# Ethernet_Controller.net
KiCad netlist of a schematic drawn in Altium Designer
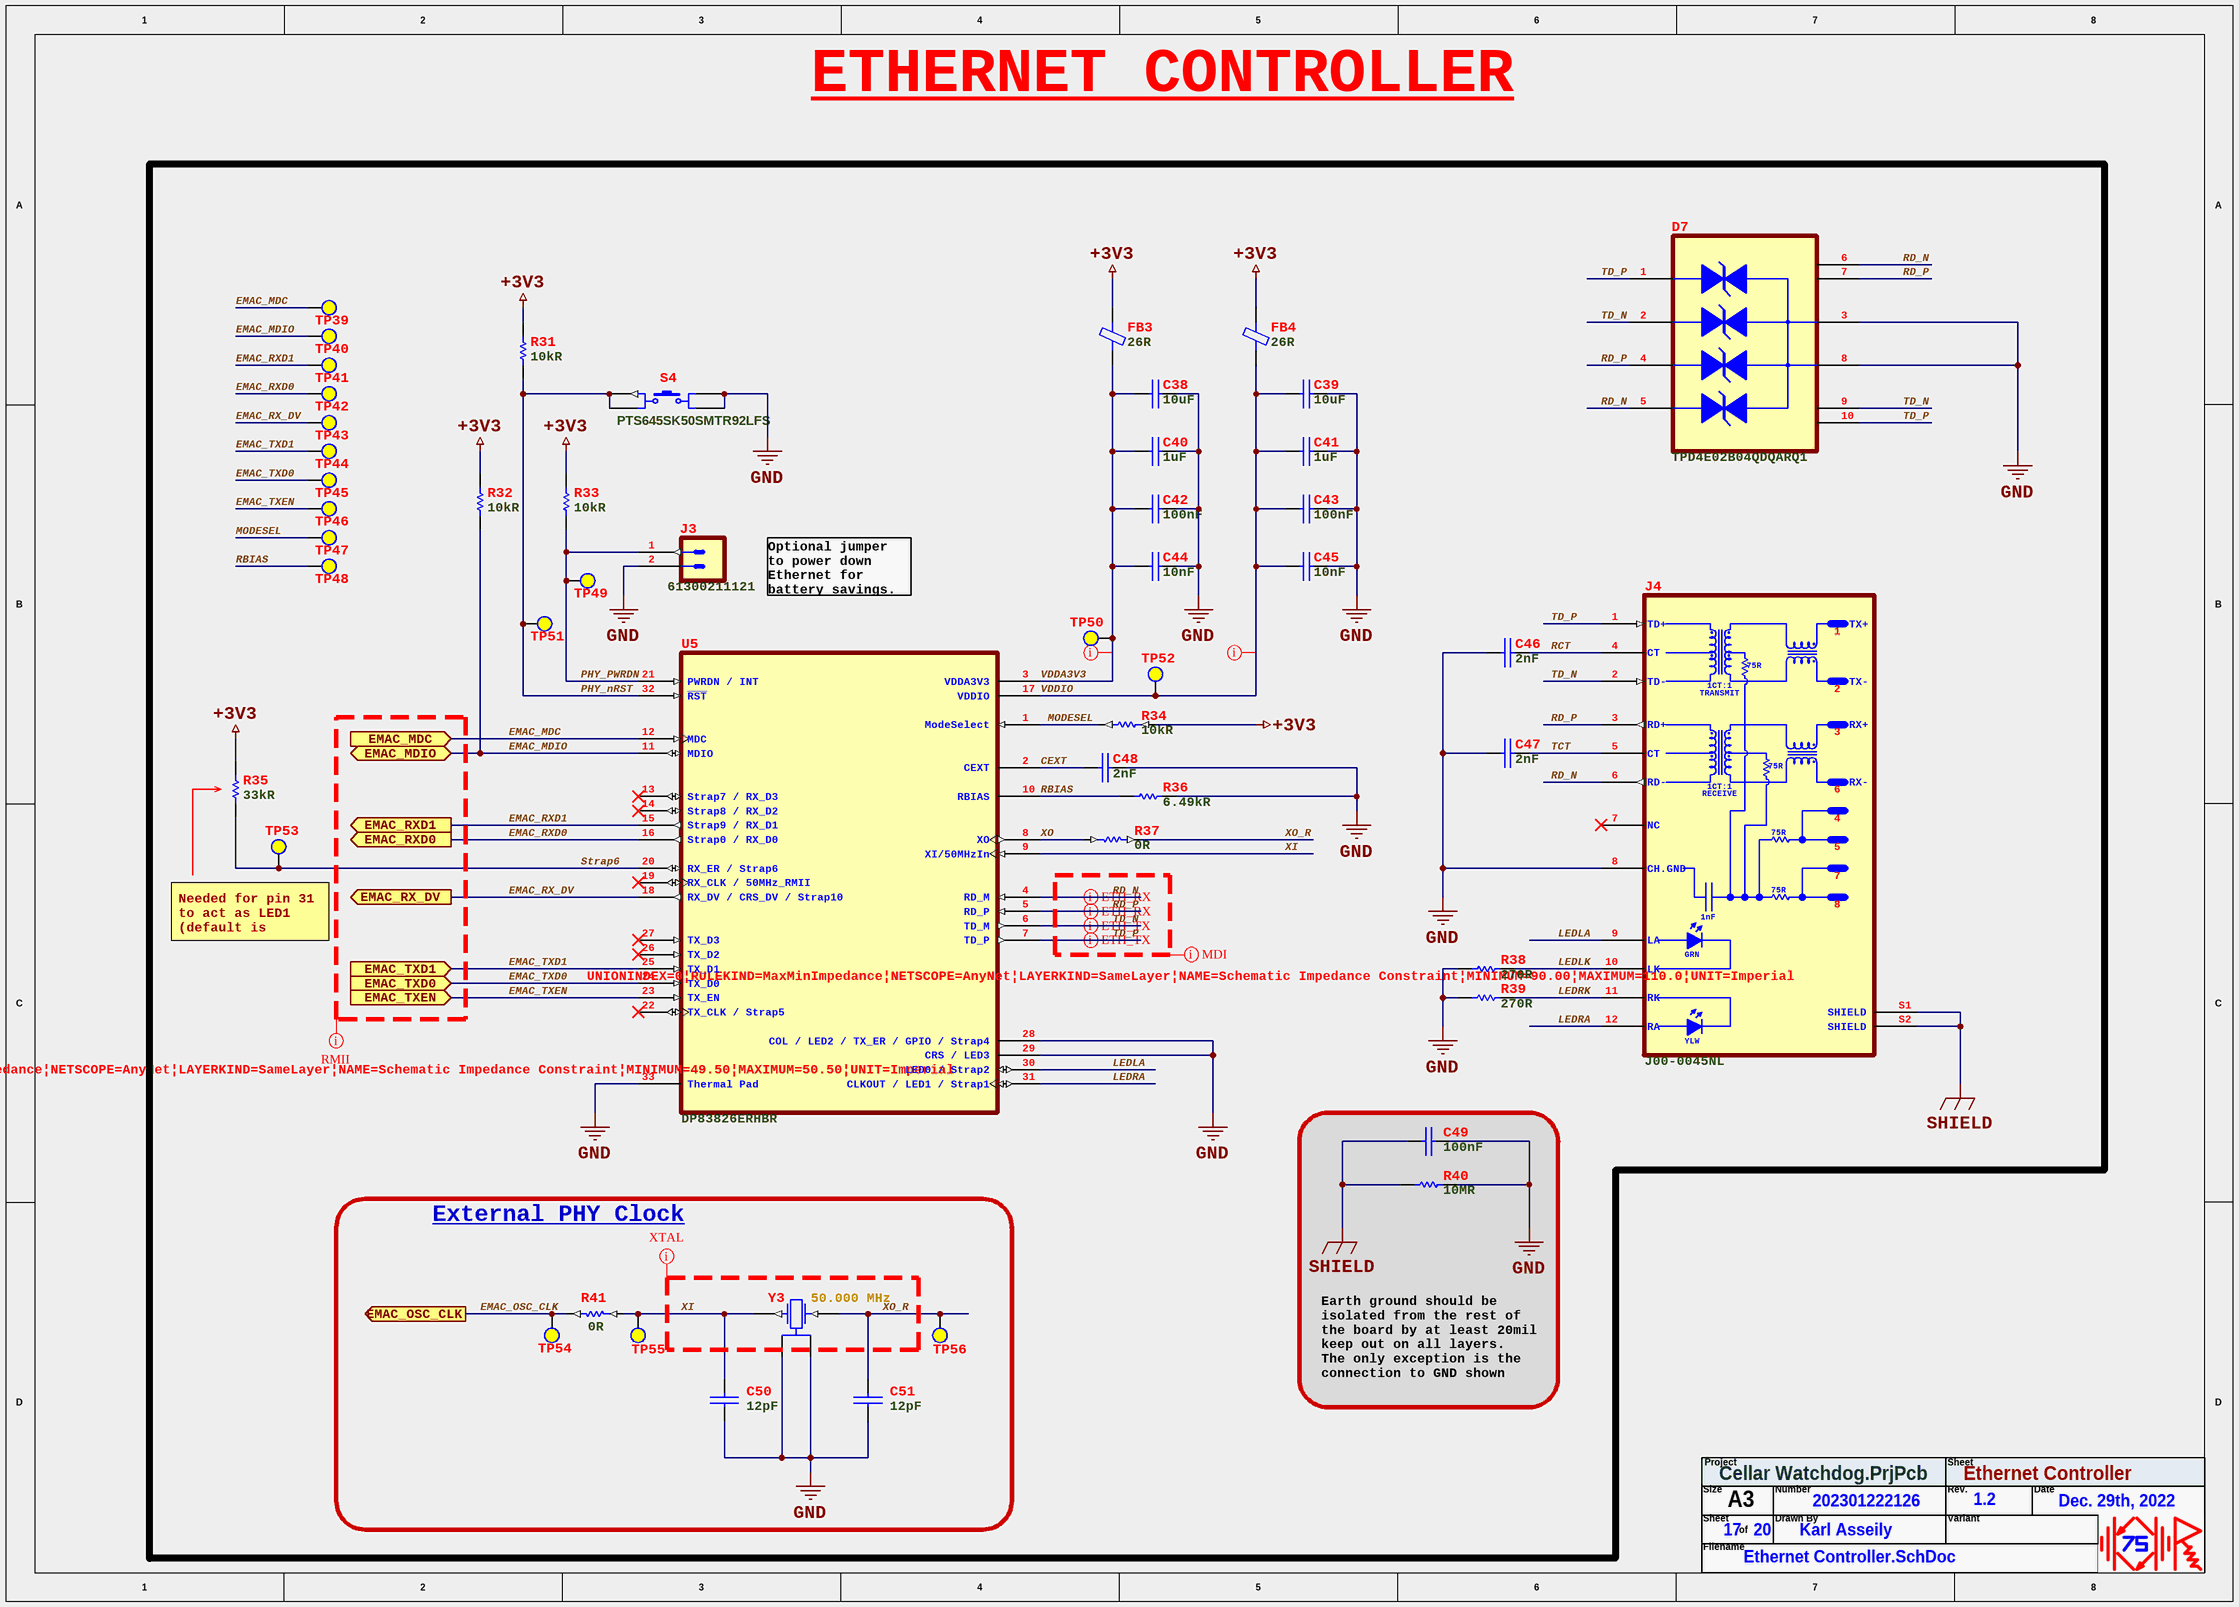
[diagram p0: Ethernet Controller.SchDoc]

(export (version "E")
  (design (tool "Eeschema 10.0.6"))
  (components
    (comp (ref "C38")
      (value "10uF")
      (footprint "CAP_1206")
      (description "10 µF ±10% 25V Ceramic Capacitor X7R 1206 (3216 Metric)")
      (fields
        (field (name "MANUFACTURER") "Yageo")
        (field (name "MANUFACTURER PART NUMBER") "CC1206KKX7R8BB106")
      )
      (libsource (lib "Cellar Watchdog") (part "CAP_10uF-25V-10%_1206"))
    )
    (comp (ref "C39")
      (value "10uF")
      (footprint "CAP_1206")
      (description "10 µF ±10% 25V Ceramic Capacitor X7R 1206 (3216 Metric)")
      (fields
        (field (name "MANUFACTURER") "Yageo")
        (field (name "MANUFACTURER PART NUMBER") "CC1206KKX7R8BB106")
      )
      (libsource (lib "Cellar Watchdog") (part "CAP_10uF-25V-10%_1206"))
    )
    (comp (ref "C40")
      (value "1uF")
      (footprint "CAP_0805")
      (description "1 µF ±10% 16V Ceramic Capacitor X7R 0603 (1608 Metric)")
      (fields
        (field (name "MANUFACTURER") "Yageo")
        (field (name "MANUFACTURER PART NUMBER") "CC0603KRX7R7BB105")
      )
      (libsource (lib "Cellar Watchdog") (part "CAP_1uF-16V-10%_0603"))
    )
    (comp (ref "C41")
      (value "1uF")
      (footprint "CAP_0805")
      (description "1 µF ±10% 16V Ceramic Capacitor X7R 0603 (1608 Metric)")
      (fields
        (field (name "MANUFACTURER") "Yageo")
        (field (name "MANUFACTURER PART NUMBER") "CC0603KRX7R7BB105")
      )
      (libsource (lib "Cellar Watchdog") (part "CAP_1uF-16V-10%_0603"))
    )
    (comp (ref "C42")
      (value "100nF")
      (footprint "CAP_0603")
      (description "0.1 µF ±10% 50V Ceramic Capacitor X7R 0603 (1608 Metric)")
      (fields
        (field (name "MANUFACTURER") "Yageo")
        (field (name "MANUFACTURER PART NUMBER") "CC0603KRX7R9BB104")
      )
      (libsource (lib "Cellar Watchdog") (part "CAP_0.1uF-50V-10%_0603"))
    )
    (comp (ref "C43")
      (value "100nF")
      (footprint "CAP_0603")
      (description "0.1 µF ±10% 50V Ceramic Capacitor X7R 0603 (1608 Metric)")
      (fields
        (field (name "MANUFACTURER") "Yageo")
        (field (name "MANUFACTURER PART NUMBER") "CC0603KRX7R9BB104")
      )
      (libsource (lib "Cellar Watchdog") (part "CAP_0.1uF-50V-10%_0603"))
    )
    (comp (ref "C44")
      (value "10nF")
      (footprint "CAP_0603")
      (description "10000 pF ±10% 50V Ceramic Capacitor X7R 0603 (1608 Metric)")
      (fields
        (field (name "MANUFACTURER") "Yageo")
        (field (name "MANUFACTURER PART NUMBER") "CC0603KRX7R9BB103")
      )
      (libsource (lib "Cellar Watchdog") (part "CAP_10nF-50V-10%_0603"))
    )
    (comp (ref "C45")
      (value "10nF")
      (footprint "CAP_0603")
      (description "10000 pF ±10% 50V Ceramic Capacitor X7R 0603 (1608 Metric)")
      (fields
        (field (name "MANUFACTURER") "Yageo")
        (field (name "MANUFACTURER PART NUMBER") "CC0603KRX7R9BB103")
      )
      (libsource (lib "Cellar Watchdog") (part "CAP_10nF-50V-10%_0603"))
    )
    (comp (ref "C46")
      (value "2nF")
      (footprint "CAP_0603")
      (description "2000 pF ±10% 50V Ceramic Capacitor X7R 0603 (1608 Metric)")
      (fields
        (field (name "MANUFACTURER") "Yageo")
        (field (name "MANUFACTURER PART NUMBER") "CC0603KRX7R9BB202")
      )
      (libsource (lib "Cellar Watchdog") (part "CAP_2nF-50V-10%_0603"))
    )
    (comp (ref "C47")
      (value "2nF")
      (footprint "CAP_0603")
      (description "2000 pF ±10% 50V Ceramic Capacitor X7R 0603 (1608 Metric)")
      (fields
        (field (name "MANUFACTURER") "Yageo")
        (field (name "MANUFACTURER PART NUMBER") "CC0603KRX7R9BB202")
      )
      (libsource (lib "Cellar Watchdog") (part "CAP_2nF-50V-10%_0603"))
    )
    (comp (ref "C48")
      (value "2nF")
      (footprint "CAP_0603")
      (description "2000 pF ±10% 50V Ceramic Capacitor X7R 0603 (1608 Metric)")
      (fields
        (field (name "MANUFACTURER") "Yageo")
        (field (name "MANUFACTURER PART NUMBER") "CC0603KRX7R9BB202")
      )
      (libsource (lib "Cellar Watchdog") (part "CAP_2nF-50V-10%_0603"))
    )
    (comp (ref "C49")
      (value "100nF")
      (footprint "CAP_1206")
      (description "0.1 µF ±5% 100V Ceramic Capacitor X7R 1206 (3216 Metric)")
      (fields
        (field (name "MANUFACTURER") "Yageo")
        (field (name "MANUFACTURER PART NUMBER") "CC1206JKX7R0BB104")
      )
      (libsource (lib "Cellar Watchdog") (part "CAP_0.1uF-100V-5%_1206"))
    )
    (comp (ref "C50")
      (value "12pF")
      (footprint "CAP_0603")
      (description "12 pF ±5% 50V Ceramic Capacitor C0G, NP0 0603 (1608 Metric)")
      (fields
        (field (name "MANUFACTURER") "Yageo")
        (field (name "MANUFACTURER PART NUMBER") "CC0603JRNPO9BN120")
      )
      (libsource (lib "Cellar Watchdog") (part "CAP_12pf-50V-5%_0603"))
    )
    (comp (ref "C51")
      (value "12pF")
      (footprint "CAP_0603")
      (description "12 pF ±5% 50V Ceramic Capacitor C0G, NP0 0603 (1608 Metric)")
      (fields
        (field (name "MANUFACTURER") "Yageo")
        (field (name "MANUFACTURER PART NUMBER") "CC0603JRNPO9BN120")
      )
      (libsource (lib "Cellar Watchdog") (part "CAP_12pf-50V-5%_0603"))
    )
    (comp (ref "D7")
      (value "TPD4E02B04QDQARQ1")
      (footprint "DIO-T-A_10-USON")
      (description "8.8V Clamp 2A (8/20µs) Ipp Tvs Diode Surface Mount 10-USON (2.5x1)")
      (fields (field (name "MANUFACTURER") "Texas Instruments"))
      (libsource (lib "Cellar Watchdog") (part "DIO-T-A-BI_5.5V-8.8V-2A_10-USON"))
    )
    (comp (ref "FB3")
      (value "26R")
      (footprint "FB_0603")
      (description "26 Ohms @ 100 MHz 1 Power Line Ferrite Bead 0603 (1608 Metric) 6A 7mOhm")
      (fields
        (field (name "MANUFACTURER") "Murata")
        (field (name "MANUFACTURER PART NUMBER") "BLM18SG260TZ1D")
      )
      (libsource (lib "Cellar Watchdog") (part "FB_26R-100MHz-6A_0603"))
    )
    (comp (ref "FB4")
      (value "26R")
      (footprint "FB_0603")
      (description "26 Ohms @ 100 MHz 1 Power Line Ferrite Bead 0603 (1608 Metric) 6A 7mOhm")
      (fields
        (field (name "MANUFACTURER") "Murata")
        (field (name "MANUFACTURER PART NUMBER") "BLM18SG260TZ1D")
      )
      (libsource (lib "Cellar Watchdog") (part "FB_26R-100MHz-6A_0603"))
    )
    (comp (ref "J3")
      (value "61300211121")
      (footprint "CON_PLG_HDR-2x1-100")
      (description "Connector Header Through Hole 2 position 0.100\" (2.54mm)")
      (fields (field (name "MANUFACTURER") "Wurth Electronics"))
      (libsource (lib "Cellar Watchdog") (part "CON-PLG-HDR_2x1-100-ST_TH"))
    )
    (comp (ref "J4")
      (value "J00-0045NL")
      (footprint "CON-RCPT_RJ_PULSE_J00-0045NL")
      (description "1 Port RJ45 Through Hole 10/100 Base-TX, AutoMDIX")
      (fields (field (name "MANUFACTURER") "Pulse"))
      (libsource (lib "Cellar Watchdog") (part "CON-RCPT_RJ_J00-0045NL"))
    )
    (comp (ref "R31")
      (value "10kR")
      (footprint "RES_0603")
      (description "10 kOhms ±1% 0.1W, 1/10W Chip Resistor 0603 (1608 Metric) Moisture Resistant Thick Film")
      (fields
        (field (name "MANUFACTURER") "Yageo")
        (field (name "MANUFACTURER PART NUMBER") "RC0603FR-0710KL")
      )
      (libsource (lib "Cellar Watchdog") (part "RES_10kR-100mW-1%_0603"))
    )
    (comp (ref "R32")
      (value "10kR")
      (footprint "RES_0603")
      (description "10 kOhms ±1% 0.1W, 1/10W Chip Resistor 0603 (1608 Metric) Moisture Resistant Thick Film")
      (fields
        (field (name "MANUFACTURER") "Yageo")
        (field (name "MANUFACTURER PART NUMBER") "RC0603FR-0710KL")
      )
      (libsource (lib "Cellar Watchdog") (part "RES_10kR-100mW-1%_0603"))
    )
    (comp (ref "R33")
      (value "10kR")
      (footprint "RES_0603")
      (description "10 kOhms ±1% 0.1W, 1/10W Chip Resistor 0603 (1608 Metric) Moisture Resistant Thick Film")
      (fields
        (field (name "MANUFACTURER") "Yageo")
        (field (name "MANUFACTURER PART NUMBER") "RC0603FR-0710KL")
      )
      (libsource (lib "Cellar Watchdog") (part "RES_10kR-100mW-1%_0603"))
    )
    (comp (ref "R34")
      (value "10kR")
      (footprint "RES_0603")
      (description "10 kOhms ±1% 0.1W, 1/10W Chip Resistor 0603 (1608 Metric) Moisture Resistant Thick Film")
      (fields
        (field (name "MANUFACTURER") "Yageo")
        (field (name "MANUFACTURER PART NUMBER") "RC0603FR-0710KL")
      )
      (libsource (lib "Cellar Watchdog") (part "RES_10kR-100mW-1%_0603"))
    )
    (comp (ref "R35")
      (value "33kR")
      (footprint "RES_0603")
      (description "33 kOhms ±1% 0.1W, 1/10W Chip Resistor 0603 (1608 Metric) Moisture Resistant Thick Film")
      (fields
        (field (name "MANUFACTURER") "Yageo")
        (field (name "MANUFACTURER PART NUMBER") "RC0603FR-0733KL")
      )
      (libsource (lib "Cellar Watchdog") (part "RES_33kR-100mW-1%_0603"))
    )
    (comp (ref "R36")
      (value "6.49kR")
      (footprint "RES_0603")
      (description "6.49 kOhms ±1% 0.1W, 1/10W Chip Resistor 0603 (1608 Metric) Moisture Resistant Thick Film")
      (fields
        (field (name "MANUFACTURER") "Yageo")
        (field (name "MANUFACTURER PART NUMBER") "RC0603FR-076K49L")
      )
      (libsource (lib "Cellar Watchdog") (part "RES_6.49kR-100mW-1%_0603"))
    )
    (comp (ref "R37")
      (value "0R")
      (footprint "RES_0603")
      (description "0 Ohms Jumper Chip Resistor 0603 (1608 Metric) Moisture Resistant Thick Film")
      (fields
        (field (name "MANUFACTURER") "Yageo")
        (field (name "MANUFACTURER PART NUMBER") "RC0603FR-070RL")
      )
      (libsource (lib "Cellar Watchdog") (part "RES_0R-100mW-1%_0603"))
    )
    (comp (ref "R38")
      (value "270R")
      (footprint "RES_0603")
      (description "270 Ohms ±1% 0.1W, 1/10W Chip Resistor 0603 (1608 Metric) Moisture Resistant Thick Film")
      (fields
        (field (name "MANUFACTURER") "Yageo")
        (field (name "MANUFACTURER PART NUMBER") "RC0603FR-07270RL")
      )
      (libsource (lib "Cellar Watchdog") (part "RES_270R-100mW-1%_0603"))
    )
    (comp (ref "R39")
      (value "270R")
      (footprint "RES_0603")
      (description "270 Ohms ±1% 0.1W, 1/10W Chip Resistor 0603 (1608 Metric) Moisture Resistant Thick Film")
      (fields
        (field (name "MANUFACTURER") "Yageo")
        (field (name "MANUFACTURER PART NUMBER") "RC0603FR-07270RL")
      )
      (libsource (lib "Cellar Watchdog") (part "RES_270R-100mW-1%_0603"))
    )
    (comp (ref "R40")
      (value "10MR")
      (footprint "RES_2512")
      (description "10 MOhms ±1% 1W Chip Resistor 2512 (6432 Metric) Moisture Resistant Thick Film")
      (fields
        (field (name "MANUFACTURER") "Yageo")
        (field (name "MANUFACTURER PART NUMBER") "RC2512FK-0710ML")
      )
      (libsource (lib "Cellar Watchdog") (part "RES_10MR-1W-1%_2512"))
    )
    (comp (ref "R41")
      (value "0R")
      (footprint "RES_0603")
      (description "0 Ohms Jumper Chip Resistor 0603 (1608 Metric) Moisture Resistant Thick Film")
      (fields
        (field (name "MANUFACTURER") "Yageo")
        (field (name "MANUFACTURER PART NUMBER") "RC0603FR-070RL")
      )
      (libsource (lib "Cellar Watchdog") (part "RES_0R-100mW-1%_0603"))
    )
    (comp (ref "S4")
      (value "PTS645SK50SMTR92LFS")
      (footprint "SW_TACTILE-SPST_PTS645SK50SMTR92LFS_SMD")
      (description "Tactile Switch SPST-NO Top Actuated Surface Mount")
      (fields (field (name "MANUFACTURER") "ITT C&K"))
      (libsource (lib "Cellar Watchdog") (part "SW4-NO-SPST_PTS645SK50SMTR92LFS_SMD"))
    )
    (comp (ref "TP39")
      (value "EMAC_MDC")
      (footprint "TEST POINT PAD")
      (description "PCB Test Point")
      (libsource (lib "Cellar Watchdog") (part "Test Point"))
    )
    (comp (ref "TP40")
      (value "EMAC_MDIO")
      (footprint "TEST POINT PAD")
      (description "PCB Test Point")
      (libsource (lib "Cellar Watchdog") (part "Test Point"))
    )
    (comp (ref "TP41")
      (value "EMAC_RXD1")
      (footprint "TEST POINT PAD")
      (description "PCB Test Point")
      (libsource (lib "Cellar Watchdog") (part "Test Point"))
    )
    (comp (ref "TP42")
      (value "EMAC_RXD0")
      (footprint "TEST POINT PAD")
      (description "PCB Test Point")
      (libsource (lib "Cellar Watchdog") (part "Test Point"))
    )
    (comp (ref "TP43")
      (value "EMAC_RX_DV")
      (footprint "TEST POINT PAD")
      (description "PCB Test Point")
      (libsource (lib "Cellar Watchdog") (part "Test Point"))
    )
    (comp (ref "TP44")
      (value "EMAC_TXD1")
      (footprint "TEST POINT PAD")
      (description "PCB Test Point")
      (libsource (lib "Cellar Watchdog") (part "Test Point"))
    )
    (comp (ref "TP45")
      (value "EMAC_TXD0")
      (footprint "TEST POINT PAD")
      (description "PCB Test Point")
      (libsource (lib "Cellar Watchdog") (part "Test Point"))
    )
    (comp (ref "TP46")
      (value "EMAC_TXEN")
      (footprint "TEST POINT PAD")
      (description "PCB Test Point")
      (libsource (lib "Cellar Watchdog") (part "Test Point"))
    )
    (comp (ref "TP47")
      (value "MODESEL")
      (footprint "TEST POINT PAD")
      (description "PCB Test Point")
      (libsource (lib "Cellar Watchdog") (part "Test Point"))
    )
    (comp (ref "TP48")
      (value "RBIAS")
      (footprint "TEST POINT PAD")
      (description "PCB Test Point")
      (libsource (lib "Cellar Watchdog") (part "Test Point"))
    )
    (comp (ref "TP49")
      (value "PHY_PWRDN")
      (footprint "TEST POINT PAD")
      (description "PCB Test Point")
      (libsource (lib "Cellar Watchdog") (part "Test Point"))
    )
    (comp (ref "TP50")
      (value "VDDA3V3")
      (footprint "TEST POINT PAD")
      (description "PCB Test Point")
      (libsource (lib "Cellar Watchdog") (part "Test Point"))
    )
    (comp (ref "TP51")
      (value "PHY_nRST")
      (footprint "TEST POINT HOLE")
      (description "PCB Test Point")
      (libsource (lib "Cellar Watchdog") (part "Test Point"))
    )
    (comp (ref "TP52")
      (value "VDDIO")
      (footprint "TEST POINT PAD")
      (description "PCB Test Point")
      (libsource (lib "Cellar Watchdog") (part "Test Point"))
    )
    (comp (ref "TP53")
      (value "Strap6")
      (footprint "TEST POINT PAD")
      (description "PCB Test Point")
      (libsource (lib "Cellar Watchdog") (part "Test Point"))
    )
    (comp (ref "TP54")
      (value "EMAC_OSC_CLK")
      (footprint "TEST POINT PAD")
      (description "PCB Test Point")
      (libsource (lib "Cellar Watchdog") (part "Test Point"))
    )
    (comp (ref "TP55")
      (value "50MHz IN EMAC")
      (footprint "TEST POINT HOLE")
      (description "PCB Test Point")
      (libsource (lib "Cellar Watchdog") (part "Test Point"))
    )
    (comp (ref "TP56")
      (value "50MHz OUT EMAC")
      (footprint "TEST POINT HOLE")
      (description "PCB Test Point")
      (libsource (lib "Cellar Watchdog") (part "Test Point"))
    )
    (comp (ref "U5")
      (value "DP83826ERHBR")
      (footprint "IC_QFN50P500X500X100-33N-D")
      (description "Ethernet Controller 10/100 Base-T/TX PHY MII, RMII Interface 32-VQFN (5x5)")
      (fields (field (name "MANUFACTURER") "Texas Instruments"))
      (libsource (lib "Cellar Watchdog") (part "IC_DP83826ERHBR"))
    )
    (comp (ref "Y3")
      (value "ECS-500-10-33-RTN-TR")
      (footprint "XTAL_ECS-500-10-33-RTN-TR")
      (description "50 MHz ±15ppm Crystal 10pF 40 Ohms 4-SMD, No Lead")
      (fields (field (name "MANUFACTURER") "ECS International") (field (name "FREQUENCY") "50.000 MHz"))
      (libsource (lib "Cellar Watchdog") (part "XTAL_50.000MHz-10pF_4-SMD"))
    )
  )
  (nets
    (net (code "1") (name "+3V3") (class "Default")
      (node (ref "FB3") (pin "2") (pinfunction "2_2") (pintype "passive"))
      (node (ref "FB4") (pin "2") (pinfunction "2_2") (pintype "passive"))
      (node (ref "R31") (pin "2") (pinfunction "2_2") (pintype "passive"))
      (node (ref "R32") (pin "2") (pinfunction "2_2") (pintype "passive"))
      (node (ref "R33") (pin "2") (pinfunction "2_2") (pintype "passive"))
      (node (ref "R34") (pin "2") (pinfunction "2_2") (pintype "passive"))
      (node (ref "R35") (pin "2") (pinfunction "2_2") (pintype "passive"))
    )
    (net (code "2") (name "/CEXT") (class "Default")
      (node (ref "C48") (pin "1") (pinfunction "1_1") (pintype "passive"))
      (node (ref "U5") (pin "2") (pinfunction "CEXT_2") (pintype "passive"))
    )
    (net (code "3") (name "/EMAC_MDC") (class "Default")
      (node (ref "TP39") (pin "TP") (pinfunction "TP_TP") (pintype "passive"))
      (node (ref "U5") (pin "12") (pinfunction "MDC_12") (pintype "input"))
    )
    (net (code "4") (name "/EMAC_MDIO") (class "Default")
      (node (ref "R32") (pin "1") (pinfunction "1_1") (pintype "passive"))
      (node (ref "TP40") (pin "TP") (pinfunction "TP_TP") (pintype "passive"))
      (node (ref "U5") (pin "11") (pinfunction "MDIO_11") (pintype "bidirectional"))
    )
    (net (code "5") (name "/EMAC_OSC_CLK") (class "Default")
      (node (ref "R41") (pin "1") (pinfunction "1_1") (pintype "input"))
      (node (ref "TP54") (pin "TP") (pinfunction "TP_TP") (pintype "passive"))
    )
    (net (code "6") (name "/EMAC_RXD0") (class "Default")
      (node (ref "TP42") (pin "TP") (pinfunction "TP_TP") (pintype "passive"))
      (node (ref "U5") (pin "16") (pinfunction "Strap0_/_RX_D0_16") (pintype "output"))
    )
    (net (code "7") (name "/EMAC_RXD1") (class "Default")
      (node (ref "TP41") (pin "TP") (pinfunction "TP_TP") (pintype "passive"))
      (node (ref "U5") (pin "15") (pinfunction "Strap9_/_RX_D1_15") (pintype "output"))
    )
    (net (code "8") (name "/EMAC_RX_DV") (class "Default")
      (node (ref "TP43") (pin "TP") (pinfunction "TP_TP") (pintype "passive"))
      (node (ref "U5") (pin "18") (pinfunction "RX_DV_/_CRS_DV_/_Strap10_18") (pintype "output"))
    )
    (net (code "9") (name "/EMAC_TXD0") (class "Default")
      (node (ref "TP45") (pin "TP") (pinfunction "TP_TP") (pintype "passive"))
      (node (ref "U5") (pin "24") (pinfunction "TX_D0_24") (pintype "input"))
    )
    (net (code "10") (name "/EMAC_TXD1") (class "Default")
      (node (ref "TP44") (pin "TP") (pinfunction "TP_TP") (pintype "passive"))
      (node (ref "U5") (pin "25") (pinfunction "TX_D1_25") (pintype "input"))
    )
    (net (code "11") (name "/EMAC_TXEN") (class "Default")
      (node (ref "TP46") (pin "TP") (pinfunction "TP_TP") (pintype "passive"))
      (node (ref "U5") (pin "23") (pinfunction "TX_EN_23") (pintype "input"))
    )
    (net (code "12") (name "/LEDLA") (class "Default")
      (node (ref "J4") (pin "9") (pinfunction "LA_9") (pintype "passive"))
      (node (ref "U5") (pin "30") (pinfunction "LED0_/_Strap2_30") (pintype "bidirectional"))
    )
    (net (code "13") (name "/LEDLK") (class "Default")
      (node (ref "J4") (pin "10") (pinfunction "LK_10") (pintype "passive"))
      (node (ref "R38") (pin "1") (pinfunction "1_1") (pintype "passive"))
    )
    (net (code "14") (name "/LEDRA") (class "Default")
      (node (ref "J4") (pin "12") (pinfunction "RA_12") (pintype "passive"))
      (node (ref "U5") (pin "31") (pinfunction "CLKOUT_/_LED1_/_Strap1_31") (pintype "bidirectional"))
    )
    (net (code "15") (name "/LEDRK") (class "Default")
      (node (ref "J4") (pin "11") (pinfunction "RK_11") (pintype "passive"))
      (node (ref "R39") (pin "1") (pinfunction "1_1") (pintype "passive"))
    )
    (net (code "16") (name "/MODESEL") (class "Default")
      (node (ref "R34") (pin "1") (pinfunction "1_1") (pintype "passive"))
      (node (ref "TP47") (pin "TP") (pinfunction "TP_TP") (pintype "passive"))
      (node (ref "U5") (pin "1") (pinfunction "ModeSelect_1") (pintype "input"))
    )
    (net (code "17") (name "/PHY_PWRDN") (class "Default")
      (node (ref "J3") (pin "1") (pinfunction "1_1") (pintype "output"))
      (node (ref "R33") (pin "1") (pinfunction "1_1") (pintype "passive"))
      (node (ref "TP49") (pin "TP") (pinfunction "TP_TP") (pintype "passive"))
      (node (ref "U5") (pin "21") (pinfunction "PWRDN_/_INT_21") (pintype "input"))
    )
    (net (code "18") (name "/PHY_nRST") (class "Default")
      (node (ref "R31") (pin "1") (pinfunction "1_1") (pintype "passive"))
      (node (ref "S4") (pin "1") (pinfunction "1_1") (pintype "output"))
      (node (ref "S4") (pin "2") (pinfunction "2_2") (pintype "passive"))
      (node (ref "TP51") (pin "TP") (pinfunction "TP_TP") (pintype "passive"))
      (node (ref "U5") (pin "32") (pinfunction "RST_32") (pintype "input"))
    )
    (net (code "19") (name "/RBIAS") (class "Default")
      (node (ref "R36") (pin "1") (pinfunction "1_1") (pintype "passive"))
      (node (ref "TP48") (pin "TP") (pinfunction "TP_TP") (pintype "passive"))
      (node (ref "U5") (pin "10") (pinfunction "RBIAS_10") (pintype "passive"))
    )
    (net (code "20") (name "/RCT") (class "Default")
      (node (ref "C46") (pin "1") (pinfunction "1_1") (pintype "passive"))
      (node (ref "J4") (pin "4") (pinfunction "CT_4") (pintype "passive"))
    )
    (net (code "21") (name "/RD_N") (class "Default")
      (node (ref "D7") (pin "5") (pinfunction "IO4_5") (pintype "passive"))
      (node (ref "D7") (pin "6") (pinfunction "NC_6") (pintype "passive"))
      (node (ref "J4") (pin "6") (pinfunction "RD-_6") (pintype "output"))
      (node (ref "U5") (pin "4") (pinfunction "RD_M_4") (pintype "input"))
    )
    (net (code "22") (name "/RD_P") (class "Default")
      (node (ref "D7") (pin "4") (pinfunction "IO3_4") (pintype "passive"))
      (node (ref "D7") (pin "7") (pinfunction "NC_7") (pintype "passive"))
      (node (ref "J4") (pin "3") (pinfunction "RD+_3") (pintype "output"))
      (node (ref "U5") (pin "5") (pinfunction "RD_P_5") (pintype "input"))
    )
    (net (code "23") (name "/Strap6") (class "Default")
      (node (ref "R35") (pin "1") (pinfunction "1_1") (pintype "passive"))
      (node (ref "TP53") (pin "TP") (pinfunction "TP_TP") (pintype "passive"))
      (node (ref "U5") (pin "20") (pinfunction "RX_ER_/_Strap6_20") (pintype "bidirectional"))
    )
    (net (code "24") (name "/TCT") (class "Default")
      (node (ref "C47") (pin "1") (pinfunction "1_1") (pintype "passive"))
      (node (ref "J4") (pin "5") (pinfunction "CT_5") (pintype "passive"))
    )
    (net (code "25") (name "/TD_N") (class "Default")
      (node (ref "D7") (pin "2") (pinfunction "IO2_2") (pintype "passive"))
      (node (ref "D7") (pin "9") (pinfunction "NC_9") (pintype "passive"))
      (node (ref "J4") (pin "2") (pinfunction "TD-_2") (pintype "input"))
      (node (ref "U5") (pin "6") (pinfunction "TD_M_6") (pintype "output"))
    )
    (net (code "26") (name "/TD_P") (class "Default")
      (node (ref "D7") (pin "1") (pinfunction "IO1_1") (pintype "passive"))
      (node (ref "D7") (pin "10") (pinfunction "NC_10") (pintype "passive"))
      (node (ref "J4") (pin "1") (pinfunction "TD+_1") (pintype "input"))
      (node (ref "U5") (pin "7") (pinfunction "TD_P_7") (pintype "output"))
    )
    (net (code "27") (name "/VDDA3V3") (class "Default")
      (node (ref "C38") (pin "1") (pinfunction "1_1") (pintype "passive"))
      (node (ref "C40") (pin "1") (pinfunction "1_1") (pintype "passive"))
      (node (ref "C42") (pin "1") (pinfunction "1_1") (pintype "passive"))
      (node (ref "C44") (pin "1") (pinfunction "1_1") (pintype "passive"))
      (node (ref "FB3") (pin "1") (pinfunction "1_1") (pintype "passive"))
      (node (ref "TP50") (pin "TP") (pinfunction "TP_TP") (pintype "passive"))
      (node (ref "U5") (pin "3") (pinfunction "VDDA3V3_3") (pintype "power_in"))
    )
    (net (code "28") (name "/VDDIO") (class "Default")
      (node (ref "C39") (pin "1") (pinfunction "1_1") (pintype "passive"))
      (node (ref "C41") (pin "1") (pinfunction "1_1") (pintype "passive"))
      (node (ref "C43") (pin "1") (pinfunction "1_1") (pintype "passive"))
      (node (ref "C45") (pin "1") (pinfunction "1_1") (pintype "passive"))
      (node (ref "FB4") (pin "1") (pinfunction "1_1") (pintype "passive"))
      (node (ref "TP52") (pin "TP") (pinfunction "TP_TP") (pintype "passive"))
      (node (ref "U5") (pin "17") (pinfunction "VDDIO_17") (pintype "power_in"))
    )
    (net (code "29") (name "/XI") (class "Default")
      (node (ref "C50") (pin "1") (pinfunction "1_1") (pintype "passive"))
      (node (ref "R41") (pin "2") (pinfunction "2_2") (pintype "output"))
      (node (ref "TP55") (pin "TP") (pinfunction "TP_TP") (pintype "passive"))
      (node (ref "U5") (pin "9") (pinfunction "XI/50MHzIn_9") (pintype "input"))
      (node (ref "Y3") (pin "1") (pinfunction "In/Out_1") (pintype "output"))
    )
    (net (code "30") (name "/XO") (class "Default")
      (node (ref "R37") (pin "1") (pinfunction "1_1") (pintype "input"))
      (node (ref "U5") (pin "8") (pinfunction "XO_8") (pintype "output"))
    )
    (net (code "31") (name "/XO_R") (class "Default")
      (node (ref "C51") (pin "1") (pinfunction "1_1") (pintype "passive"))
      (node (ref "R37") (pin "2") (pinfunction "2_2") (pintype "output"))
      (node (ref "TP56") (pin "TP") (pinfunction "TP_TP") (pintype "passive"))
      (node (ref "Y3") (pin "3") (pinfunction "Out/In_3") (pintype "input"))
    )
    (net (code "32") (name "GND") (class "Default")
      (node (ref "C38") (pin "2") (pinfunction "2_2") (pintype "passive"))
      (node (ref "C39") (pin "2") (pinfunction "2_2") (pintype "passive"))
      (node (ref "C40") (pin "2") (pinfunction "2_2") (pintype "passive"))
      (node (ref "C41") (pin "2") (pinfunction "2_2") (pintype "passive"))
      (node (ref "C42") (pin "2") (pinfunction "2_2") (pintype "passive"))
      (node (ref "C43") (pin "2") (pinfunction "2_2") (pintype "passive"))
      (node (ref "C44") (pin "2") (pinfunction "2_2") (pintype "passive"))
      (node (ref "C45") (pin "2") (pinfunction "2_2") (pintype "passive"))
      (node (ref "C46") (pin "2") (pinfunction "2_2") (pintype "passive"))
      (node (ref "C47") (pin "2") (pinfunction "2_2") (pintype "passive"))
      (node (ref "C48") (pin "2") (pinfunction "2_2") (pintype "passive"))
      (node (ref "C49") (pin "2") (pinfunction "2_2") (pintype "passive"))
      (node (ref "C50") (pin "2") (pinfunction "2_2") (pintype "passive"))
      (node (ref "C51") (pin "2") (pinfunction "2_2") (pintype "passive"))
      (node (ref "D7") (pin "3") (pinfunction "GND_3") (pintype "power_in"))
      (node (ref "D7") (pin "8") (pinfunction "GND_8") (pintype "power_in"))
      (node (ref "J3") (pin "2") (pinfunction "2_2") (pintype "power_in"))
      (node (ref "J4") (pin "8") (pinfunction "CH.GND_8") (pintype "power_in"))
      (node (ref "R36") (pin "2") (pinfunction "2_2") (pintype "passive"))
      (node (ref "R38") (pin "2") (pinfunction "2_2") (pintype "passive"))
      (node (ref "R39") (pin "2") (pinfunction "2_2") (pintype "passive"))
      (node (ref "R40") (pin "2") (pinfunction "2_2") (pintype "passive"))
      (node (ref "S4") (pin "3") (pinfunction "3_3") (pintype "passive"))
      (node (ref "S4") (pin "4") (pinfunction "4_4") (pintype "passive"))
      (node (ref "U5") (pin "28") (pinfunction "COL_/_LED2_/_TX_ER_/_GPIO_/_Strap4_28") (pintype "passive"))
      (node (ref "U5") (pin "29") (pinfunction "CRS_/_LED3_29") (pintype "passive"))
      (node (ref "U5") (pin "33") (pinfunction "Thermal_Pad_33") (pintype "power_in"))
      (node (ref "Y3") (pin "2") (pinfunction "GND_2") (pintype "power_in"))
      (node (ref "Y3") (pin "4") (pinfunction "GND_4") (pintype "power_in"))
    )
    (net (code "33") (name "SHIELD") (class "Default")
      (node (ref "C49") (pin "1") (pinfunction "1_1") (pintype "passive"))
      (node (ref "J4") (pin "S1") (pinfunction "SHIELD_S1") (pintype "passive"))
      (node (ref "J4") (pin "S2") (pinfunction "SHIELD_S2") (pintype "passive"))
      (node (ref "R40") (pin "1") (pinfunction "1_1") (pintype "passive"))
    )
    (net (code "34") (name "unconnected-(J4-NC-Pad7)") (class "Default")
      (node (ref "J4") (pin "7") (pinfunction "NC_7") (pintype "passive+no_connect"))
    )
    (net (code "35") (name "unconnected-(U5-RX_CLK_{slash}_50MHz_RMII-Pad19)") (class "Default")
      (node (ref "U5") (pin "19") (pinfunction "RX_CLK_/_50MHz_RMII_19") (pintype "bidirectional+no_connect"))
    )
    (net (code "36") (name "unconnected-(U5-Strap7_{slash}_RX_D3-Pad13)") (class "Default")
      (node (ref "U5") (pin "13") (pinfunction "Strap7_/_RX_D3_13") (pintype "bidirectional+no_connect"))
    )
    (net (code "37") (name "unconnected-(U5-Strap8_{slash}_RX_D2-Pad14)") (class "Default")
      (node (ref "U5") (pin "14") (pinfunction "Strap8_/_RX_D2_14") (pintype "bidirectional+no_connect"))
    )
    (net (code "38") (name "unconnected-(U5-TX_CLK_{slash}_Strap5-Pad22)") (class "Default")
      (node (ref "U5") (pin "22") (pinfunction "TX_CLK_/_Strap5_22") (pintype "bidirectional+no_connect"))
    )
    (net (code "39") (name "unconnected-(U5-TX_D2-Pad26)") (class "Default")
      (node (ref "U5") (pin "26") (pinfunction "TX_D2_26") (pintype "input+no_connect"))
    )
    (net (code "40") (name "unconnected-(U5-TX_D3-Pad27)") (class "Default")
      (node (ref "U5") (pin "27") (pinfunction "TX_D3_27") (pintype "input+no_connect"))
    )
  )
)
